# nodeMCU_vs_motor.net
KiCad netlist of a schematic drawn in Altium Designer
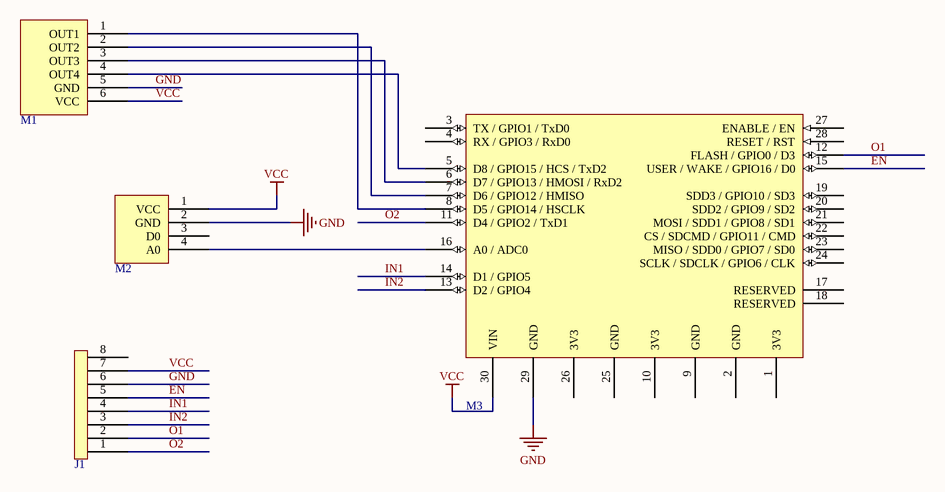
[diagram p0: nodeMCU vs motor.SchDoc]

(export (version "E")
  (design (tool "Eeschema 10.0.6"))
  (components
    (comp (ref "J1") (value "JP_8") (footprint "JP_8") (libsource (lib "LuongTanDat") (part "JP_8")))
    (comp (ref "M1")
      (value "Module TTP224")
      (footprint "MODULE_TTP224")
      (libsource (lib "LuongTanDat") (part "Module TTP224"))
    )
    (comp (ref "M2")
      (value "Module LDR")
      (footprint "MODULE LDR")
      (libsource (lib "LuongTanDat") (part "Module LDR"))
    )
    (comp (ref "M3")
      (value "NodeMCU")
      (footprint "NODEMCU_V1.0_LABEL_OUTSIDE")
      (description "NodeMCU DevKit v1.0")
      (libsource (lib "LuongTanDat") (part "NodeMCU-v1.0"))
    )
  )
  (nets
    (net (code "1") (name "/EN") (class "Default")
      (node (ref "J1") (pin "5") (pinfunction "5_5") (pintype "passive"))
      (node (ref "M3") (pin "15") (pinfunction "USER_/_WAKE_/_GPIO16_/_D0_15") (pintype "bidirectional"))
    )
    (net (code "2") (name "/IN1") (class "Default")
      (node (ref "J1") (pin "4") (pinfunction "4_4") (pintype "passive"))
      (node (ref "M3") (pin "14") (pinfunction "D1_/_GPIO5_14") (pintype "bidirectional"))
    )
    (net (code "3") (name "/IN2") (class "Default")
      (node (ref "J1") (pin "3") (pinfunction "3_3") (pintype "passive"))
      (node (ref "M3") (pin "13") (pinfunction "D2_/_GPIO4_13") (pintype "bidirectional"))
    )
    (net (code "4") (name "/O1") (class "Default")
      (node (ref "J1") (pin "2") (pinfunction "2_2") (pintype "passive"))
      (node (ref "M3") (pin "12") (pinfunction "FLASH_/_GPIO0_/_D3_12") (pintype "bidirectional"))
    )
    (net (code "5") (name "/O2") (class "Default")
      (node (ref "J1") (pin "1") (pinfunction "1_1") (pintype "passive"))
      (node (ref "M3") (pin "11") (pinfunction "D4_/_GPIO2_/_TxD1_11") (pintype "bidirectional"))
    )
    (net (code "6") (name "GND") (class "Default")
      (node (ref "J1") (pin "6") (pinfunction "6_6") (pintype "passive"))
      (node (ref "M1") (pin "5") (pinfunction "GND_5") (pintype "passive"))
      (node (ref "M2") (pin "2") (pinfunction "GND_2") (pintype "passive"))
      (node (ref "M3") (pin "29") (pinfunction "GND_29") (pintype "passive"))
    )
    (net (code "7") (name "Net-(M1-OUT1)") (class "Default")
      (node (ref "M1") (pin "1") (pinfunction "OUT1_1") (pintype "passive"))
      (node (ref "M3") (pin "8") (pinfunction "D5_/_GPIO14_/_HSCLK_8") (pintype "bidirectional"))
    )
    (net (code "8") (name "Net-(M1-OUT2)") (class "Default")
      (node (ref "M1") (pin "2") (pinfunction "OUT2_2") (pintype "passive"))
      (node (ref "M3") (pin "7") (pinfunction "D6_/_GPIO12_/_HMISO_7") (pintype "bidirectional"))
    )
    (net (code "9") (name "Net-(M1-OUT3)") (class "Default")
      (node (ref "M1") (pin "3") (pinfunction "OUT3_3") (pintype "passive"))
      (node (ref "M3") (pin "6") (pinfunction "D7_/_GPIO13_/_HMOSI_/_RxD2_6") (pintype "bidirectional"))
    )
    (net (code "10") (name "Net-(M1-OUT4)") (class "Default")
      (node (ref "M1") (pin "4") (pinfunction "OUT4_4") (pintype "passive"))
      (node (ref "M3") (pin "5") (pinfunction "D8_/_GPIO15_/_HCS_/_TxD2_5") (pintype "bidirectional"))
    )
    (net (code "11") (name "Net-(M2-A0)") (class "Default")
      (node (ref "M2") (pin "4") (pinfunction "A0_4") (pintype "passive"))
      (node (ref "M3") (pin "16") (pinfunction "A0_/_ADC0_16") (pintype "bidirectional"))
    )
    (net (code "12") (name "VCC") (class "Default")
      (node (ref "J1") (pin "7") (pinfunction "7_7") (pintype "passive"))
      (node (ref "M1") (pin "6") (pinfunction "VCC_6") (pintype "passive"))
      (node (ref "M2") (pin "1") (pinfunction "VCC_1") (pintype "passive"))
      (node (ref "M3") (pin "30") (pinfunction "VIN_30") (pintype "passive"))
    )
    (net (code "13") (name "unconnected-(J1-Pad8)") (class "Default")
      (node (ref "J1") (pin "8") (pinfunction "8_8") (pintype "passive"))
    )
    (net (code "14") (name "unconnected-(M2-D0-Pad3)") (class "Default")
      (node (ref "M2") (pin "3") (pinfunction "D0_3") (pintype "passive"))
    )
    (net (code "15") (name "unconnected-(M3-3V3-Pad1)") (class "Default")
      (node (ref "M3") (pin "1") (pinfunction "3V3_1") (pintype "passive"))
    )
    (net (code "16") (name "unconnected-(M3-3V3-Pad10)") (class "Default")
      (node (ref "M3") (pin "10") (pinfunction "3V3_10") (pintype "passive"))
    )
    (net (code "17") (name "unconnected-(M3-3V3-Pad26)") (class "Default")
      (node (ref "M3") (pin "26") (pinfunction "3V3_26") (pintype "passive"))
    )
    (net (code "18") (name "unconnected-(M3-CS_{slash}_SDCMD_{slash}_GPIO11_{slash}_CMD-Pad22)") (class "Default")
      (node (ref "M3") (pin "22") (pinfunction "CS_/_SDCMD_/_GPIO11_/_CMD_22") (pintype "bidirectional"))
    )
    (net (code "19") (name "unconnected-(M3-ENABLE_{slash}_EN-Pad27)") (class "Default")
      (node (ref "M3") (pin "27") (pinfunction "ENABLE_/_EN_27") (pintype "input"))
    )
    (net (code "20") (name "unconnected-(M3-GND-Pad2)") (class "Default")
      (node (ref "M3") (pin "2") (pinfunction "GND_2") (pintype "passive"))
    )
    (net (code "21") (name "unconnected-(M3-GND-Pad9)") (class "Default")
      (node (ref "M3") (pin "9") (pinfunction "GND_9") (pintype "passive"))
    )
    (net (code "22") (name "unconnected-(M3-GND-Pad25)") (class "Default")
      (node (ref "M3") (pin "25") (pinfunction "GND_25") (pintype "passive"))
    )
    (net (code "23") (name "unconnected-(M3-MISO_{slash}_SDD0_{slash}_GPIO7_{slash}_SD0-Pad23)") (class "Default")
      (node (ref "M3") (pin "23") (pinfunction "MISO_/_SDD0_/_GPIO7_/_SD0_23") (pintype "bidirectional"))
    )
    (net (code "24") (name "unconnected-(M3-MOSI_{slash}_SDD1_{slash}_GPIO8_{slash}_SD1-Pad21)") (class "Default")
      (node (ref "M3") (pin "21") (pinfunction "MOSI_/_SDD1_/_GPIO8_/_SD1_21") (pintype "bidirectional"))
    )
    (net (code "25") (name "unconnected-(M3-RESERVED-Pad17)") (class "Default")
      (node (ref "M3") (pin "17") (pinfunction "RESERVED_17") (pintype "passive"))
    )
    (net (code "26") (name "unconnected-(M3-RESERVED-Pad18)") (class "Default")
      (node (ref "M3") (pin "18") (pinfunction "RESERVED_18") (pintype "passive"))
    )
    (net (code "27") (name "unconnected-(M3-RESET_{slash}_RST-Pad28)") (class "Default")
      (node (ref "M3") (pin "28") (pinfunction "RESET_/_RST_28") (pintype "input"))
    )
    (net (code "28") (name "unconnected-(M3-RX_{slash}_GPIO3_{slash}_RxD0-Pad4)") (class "Default")
      (node (ref "M3") (pin "4") (pinfunction "RX_/_GPIO3_/_RxD0_4") (pintype "bidirectional"))
    )
    (net (code "29") (name "unconnected-(M3-SCLK_{slash}_SDCLK_{slash}_GPIO6_{slash}_CLK-Pad24)") (class "Default")
      (node (ref "M3") (pin "24") (pinfunction "SCLK_/_SDCLK_/_GPIO6_/_CLK_24") (pintype "bidirectional"))
    )
    (net (code "30") (name "unconnected-(M3-SDD2_{slash}_GPIO9_{slash}_SD2-Pad20)") (class "Default")
      (node (ref "M3") (pin "20") (pinfunction "SDD2_/_GPIO9_/_SD2_20") (pintype "bidirectional"))
    )
    (net (code "31") (name "unconnected-(M3-SDD3_{slash}_GPIO10_{slash}_SD3-Pad19)") (class "Default")
      (node (ref "M3") (pin "19") (pinfunction "SDD3_/_GPIO10_/_SD3_19") (pintype "bidirectional"))
    )
    (net (code "32") (name "unconnected-(M3-TX_{slash}_GPIO1_{slash}_TxD0-Pad3)") (class "Default")
      (node (ref "M3") (pin "3") (pinfunction "TX_/_GPIO1_/_TxD0_3") (pintype "bidirectional"))
    )
  )
)
